# STLINK_V2-1.net
KiCad netlist of a schematic drawn in Altium Designer
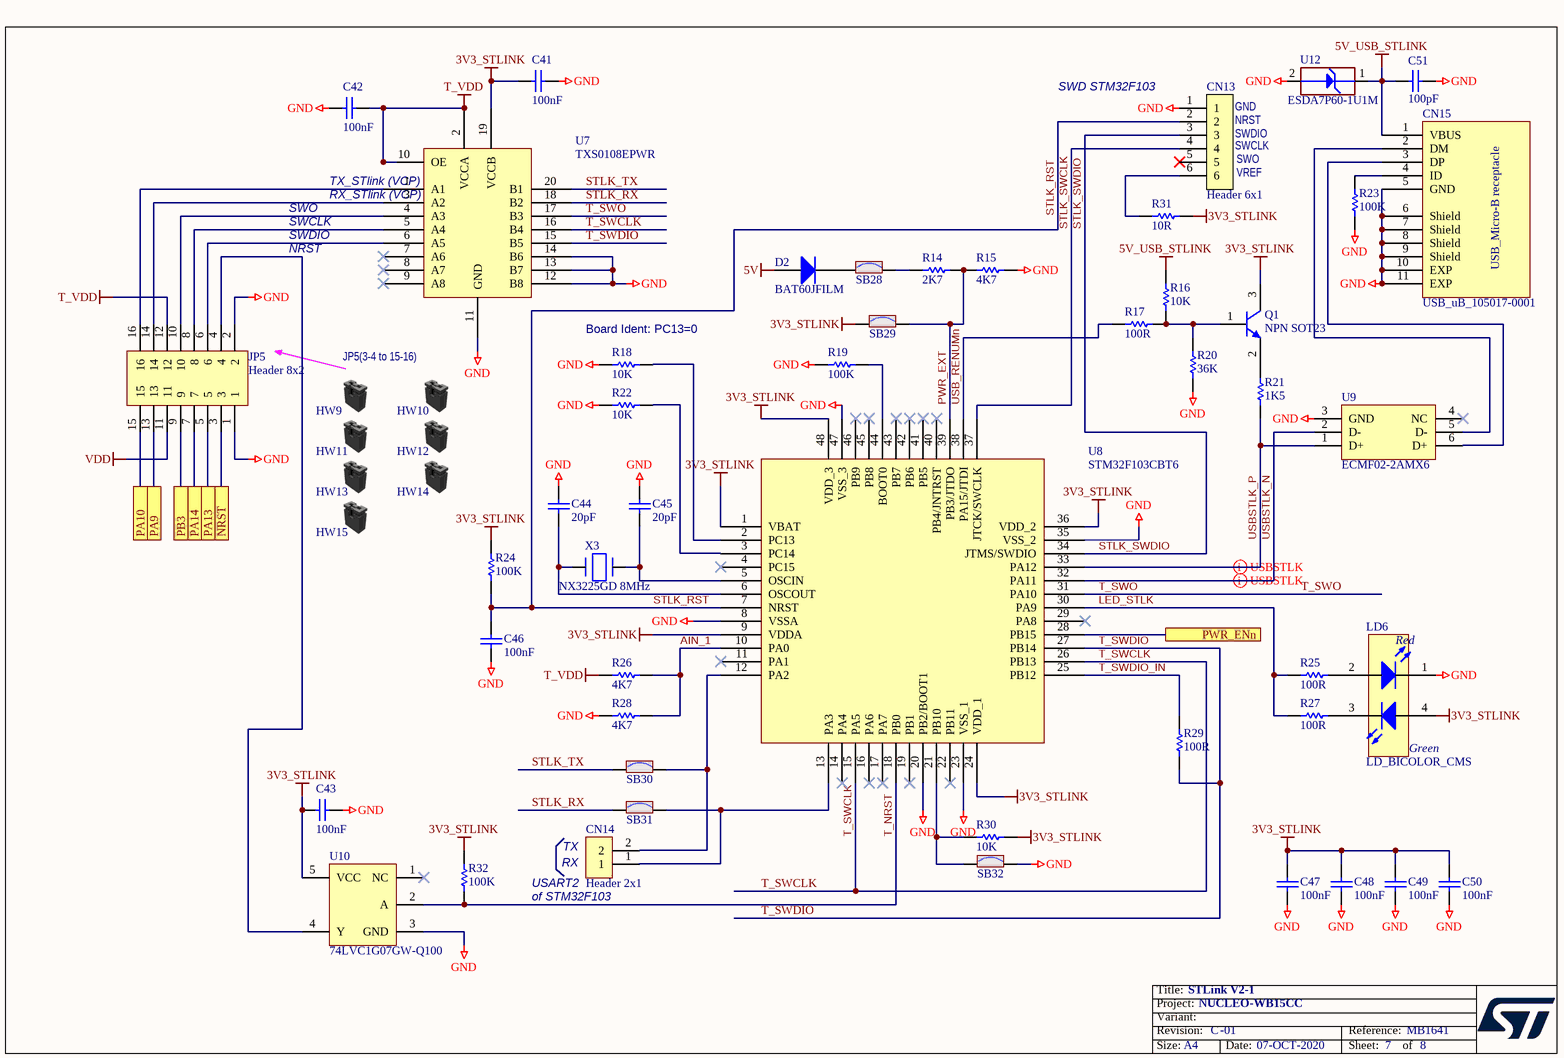
[diagram p0: STLINK_V2-1.SCHDOC]

(export (version "E")
  (design (tool "Eeschema 10.0.6"))
  (components
    (comp (ref "C41")
      (value "100nF")
      (footprint "C0402")
      (description "Capacitor, MLCC, 100nF, 16V, X7R, +/-10%, 0402, T=0.5mm")
      (fields
        (field (name "INTERNAL_PART_NUMBER") "MCD-00006")
        (field (name "MANUFACTURER_PART_NUMBER") "CC0402KRX7R7BB104")
      )
      (libsource (lib "MCD_PARTS_database") (part "Capacitor"))
    )
    (comp (ref "C42")
      (value "100nF")
      (footprint "C0402")
      (description "Capacitor, MLCC, 100nF, 16V, X7R, +/-10%, 0402, T=0.5mm")
      (fields
        (field (name "INTERNAL_PART_NUMBER") "MCD-00006")
        (field (name "MANUFACTURER_PART_NUMBER") "CC0402KRX7R7BB104")
      )
      (libsource (lib "MCD_PARTS_database") (part "Capacitor"))
    )
    (comp (ref "C43")
      (value "100nF")
      (footprint "C0402")
      (description "Capacitor, MLCC, 100nF, 16V, X7R, +/-10%, 0402, T=0.5mm")
      (fields
        (field (name "INTERNAL_PART_NUMBER") "MCD-00006")
        (field (name "MANUFACTURER_PART_NUMBER") "CC0402KRX7R7BB104")
      )
      (libsource (lib "MCD_PARTS_database") (part "Capacitor"))
    )
    (comp (ref "C44")
      (value "20pF")
      (footprint "C0402")
      (description "Capacitor, MLCC, 20pF, 50V, NPO, +/- 5%, 0402, T=0,5mm")
      (fields
        (field (name "INTERNAL_PART_NUMBER") "MCD-00016")
        (field (name "MANUFACTURER_PART_NUMBER") "CC0402JRNPO9BN200")
      )
      (libsource (lib "MCD_PARTS_database") (part "Capacitor"))
    )
    (comp (ref "C45")
      (value "20pF")
      (footprint "C0402")
      (description "Capacitor, MLCC, 20pF, 50V, NPO, +/- 5%, 0402, T=0,5mm")
      (fields
        (field (name "INTERNAL_PART_NUMBER") "MCD-00016")
        (field (name "MANUFACTURER_PART_NUMBER") "CC0402JRNPO9BN200")
      )
      (libsource (lib "MCD_PARTS_database") (part "Capacitor"))
    )
    (comp (ref "C46")
      (value "100nF")
      (footprint "C0402")
      (description "Capacitor, MLCC, 100nF, 16V, X7R, +/-10%, 0402, T=0.5mm")
      (fields
        (field (name "INTERNAL_PART_NUMBER") "MCD-00006")
        (field (name "MANUFACTURER_PART_NUMBER") "CC0402KRX7R7BB104")
      )
      (libsource (lib "MCD_PARTS_database") (part "Capacitor"))
    )
    (comp (ref "C47")
      (value "100nF")
      (footprint "C0402")
      (description "Capacitor, MLCC, 100nF, 16V, X7R, +/-10%, 0402, T=0.5mm")
      (fields
        (field (name "INTERNAL_PART_NUMBER") "MCD-00006")
        (field (name "MANUFACTURER_PART_NUMBER") "CC0402KRX7R7BB104")
      )
      (libsource (lib "MCD_PARTS_database") (part "Capacitor"))
    )
    (comp (ref "C48")
      (value "100nF")
      (footprint "C0402")
      (description "Capacitor, MLCC, 100nF, 16V, X7R, +/-10%, 0402, T=0.5mm")
      (fields
        (field (name "INTERNAL_PART_NUMBER") "MCD-00006")
        (field (name "MANUFACTURER_PART_NUMBER") "CC0402KRX7R7BB104")
      )
      (libsource (lib "MCD_PARTS_database") (part "Capacitor"))
    )
    (comp (ref "C49")
      (value "100nF")
      (footprint "C0402")
      (description "Capacitor, MLCC, 100nF, 16V, X7R, +/-10%, 0402, T=0.5mm")
      (fields
        (field (name "INTERNAL_PART_NUMBER") "MCD-00006")
        (field (name "MANUFACTURER_PART_NUMBER") "CC0402KRX7R7BB104")
      )
      (libsource (lib "MCD_PARTS_database") (part "Capacitor"))
    )
    (comp (ref "C50")
      (value "100nF")
      (footprint "C0402")
      (description "Capacitor, MLCC, 100nF, 16V, X7R, +/-10%, 0402, T=0.5mm")
      (fields
        (field (name "INTERNAL_PART_NUMBER") "MCD-00006")
        (field (name "MANUFACTURER_PART_NUMBER") "CC0402KRX7R7BB104")
      )
      (libsource (lib "MCD_PARTS_database") (part "Capacitor"))
    )
    (comp (ref "C51")
      (value "100pF")
      (footprint "C0402")
      (description "Capacitor,MLCC,100pF,50V,NPO,+/-5%,0402,T=0,5mm")
      (fields
        (field (name "INTERNAL_PART_NUMBER") "MCD-00205")
        (field (name "MANUFACTURER_PART_NUMBER") "CC0402JRNPO9BN101")
      )
      (libsource (lib "MCD_PARTS_database") (part "Capacitor"))
    )
    (comp (ref "CN13")
      (value "Header 6x1")
      (footprint "CON_SAMTEC_TSW-106-07-X-S")
      (description "Header, 6x1, 2,54mm, VR, TH, Height 5.84mm/2.54mm")
      (fields
        (field (name "INTERNAL_PART_NUMBER") "MCD-00212")
        (field (name "MANUFACTURER_PART_NUMBER") "TSW-106-07-G-S")
      )
      (libsource (lib "MCD_PARTS_database") (part "Header 6x1"))
    )
    (comp (ref "CN14")
      (value "Header 2x1")
      (footprint "CON_SAMTEC_TSW-102-07-G-S")
      (description "Header, 2x1, 2,54mm, VR, TH, Height 5.84mm/2.54mm")
      (fields
        (field (name "INTERNAL_PART_NUMBER") "MCD-00032")
        (field (name "MANUFACTURER_PART_NUMBER") "TSW-102-07-G-S")
      )
      (libsource (lib "MCD_PARTS_database") (part "Header 2x1"))
    )
    (comp (ref "CN15")
      (value "USB_uB_105017-0001")
      (footprint "CON_USBMICROB_MOLEX_105017-0001_H2P90")
      (description "USB-MICRO-B, 0.65mm, RA, SMT, Bottom Mount,")
      (fields
        (field (name "INTERNAL_PART_NUMBER") "MCD-00028")
        (field (name "MANUFACTURER_PART_NUMBER") "1050170001")
      )
      (libsource (lib "MCD_PARTS_database") (part "USB_uB_105017.0001"))
    )
    (comp (ref "D2")
      (value "BAT60JFILM")
      (footprint "DIO_SOD323")
      (fields
        (field (name "INTERNAL_PART_NUMBER") "MCD-00034")
        (field (name "MANUFACTURER") "STMICROELECTRONICS")
        (field (name "BMS_PART_NUMBER") "9151097")
      )
      (libsource (lib "MCD_PARTS_database") (part "BAT60JFILM"))
    )
    (comp (ref "HW9")
      (value "Shunt Black 2.54mm")
      (description "SHUNT 2.54mm BLACK")
      (fields
        (field (name "INTERNAL_PART_NUMBER") "MCD-00043")
        (field (name "MANUFACTURER_PART_NUMBER") "SNT-100-BK-G")
      )
      (libsource (lib "MCD_PARTS_database") (part "Shunt Black 2.54mm"))
    )
    (comp (ref "HW10")
      (value "Shunt Black 2.54mm")
      (description "SHUNT 2.54mm BLACK")
      (fields
        (field (name "INTERNAL_PART_NUMBER") "MCD-00043")
        (field (name "MANUFACTURER_PART_NUMBER") "SNT-100-BK-G")
      )
      (libsource (lib "MCD_PARTS_database") (part "Shunt Black 2.54mm"))
    )
    (comp (ref "HW11")
      (value "Shunt Black 2.54mm")
      (description "SHUNT 2.54mm BLACK")
      (fields
        (field (name "INTERNAL_PART_NUMBER") "MCD-00043")
        (field (name "MANUFACTURER_PART_NUMBER") "SNT-100-BK-G")
      )
      (libsource (lib "MCD_PARTS_database") (part "Shunt Black 2.54mm"))
    )
    (comp (ref "HW12")
      (value "Shunt Black 2.54mm")
      (description "SHUNT 2.54mm BLACK")
      (fields
        (field (name "INTERNAL_PART_NUMBER") "MCD-00043")
        (field (name "MANUFACTURER_PART_NUMBER") "SNT-100-BK-G")
      )
      (libsource (lib "MCD_PARTS_database") (part "Shunt Black 2.54mm"))
    )
    (comp (ref "HW13")
      (value "Shunt Black 2.54mm")
      (description "SHUNT 2.54mm BLACK")
      (fields
        (field (name "INTERNAL_PART_NUMBER") "MCD-00043")
        (field (name "MANUFACTURER_PART_NUMBER") "SNT-100-BK-G")
      )
      (libsource (lib "MCD_PARTS_database") (part "Shunt Black 2.54mm"))
    )
    (comp (ref "HW14")
      (value "Shunt Black 2.54mm")
      (description "SHUNT 2.54mm BLACK")
      (fields
        (field (name "INTERNAL_PART_NUMBER") "MCD-00043")
        (field (name "MANUFACTURER_PART_NUMBER") "SNT-100-BK-G")
      )
      (libsource (lib "MCD_PARTS_database") (part "Shunt Black 2.54mm"))
    )
    (comp (ref "HW15")
      (value "Shunt Black 2.54mm")
      (description "SHUNT 2.54mm BLACK")
      (fields
        (field (name "INTERNAL_PART_NUMBER") "MCD-00043")
        (field (name "MANUFACTURER_PART_NUMBER") "SNT-100-BK-G")
      )
      (libsource (lib "MCD_PARTS_database") (part "Shunt Black 2.54mm"))
    )
    (comp (ref "JP5")
      (value "Header 8x2")
      (footprint "CON_SAMTEC_TSW-108-07-X-D")
      (description "Header, 8x2, 2,54mm, VR, TH, Height 5.84mm/2.54mm")
      (fields
        (field (name "INTERNAL_PART_NUMBER") "MCD-02061")
        (field (name "MANUFACTURER_PART_NUMBER") "TSW-108-07-G-D")
      )
      (libsource (lib "MCD_PARTS_database") (part "Header 8x2"))
    )
    (comp (ref "LD6")
      (value "LD_BICOLOR_CMS")
      (footprint "LED_BI-GR_HSMF-A201-A00J1")
      (description "LED Bicolor")
      (fields
        (field (name "INTERNAL_PART_NUMBER") "MCD-00051")
        (field (name "MANUFACTURER_PART_NUMBER") "HSMF-A201-A00J1")
      )
      (libsource (lib "MCD_PARTS_database") (part "LD_BICOLOR_CMS"))
    )
    (comp (ref "Q1")
      (value "NPN SOT23")
      (footprint "NPN_SOT23")
      (description "NPN Bipolar Transistor")
      (fields
        (field (name "INTERNAL_PART_NUMBER") "MCD-00073")
        (field (name "MANUFACTURER_PART_NUMBER") "BSR14")
      )
      (libsource (lib "MCD_PARTS_database") (part "9013-SOT23"))
    )
    (comp (ref "R14")
      (value "2K7")
      (footprint "R0402")
      (description "Resistor,2K7,0402,1%,1/16W")
      (fields
        (field (name "INTERNAL_PART_NUMBER") "MCD-00055")
        (field (name "MANUFACTURER_PART_NUMBER") "RC0402FR-072K7L")
      )
      (libsource (lib "MCD_PARTS_database") (part "Resistor"))
    )
    (comp (ref "R15")
      (value "4K7")
      (footprint "R0402")
      (description "Resistor,4K7,0402,1%,1/16W")
      (fields
        (field (name "INTERNAL_PART_NUMBER") "MCD-00065")
        (field (name "MANUFACTURER_PART_NUMBER") "RC0402FR-074K7L")
      )
      (libsource (lib "MCD_PARTS_database") (part "Resistor"))
    )
    (comp (ref "R16")
      (value "10K")
      (footprint "R0402")
      (description "Resistor,10K,0402,1%,1/16W")
      (fields
        (field (name "INTERNAL_PART_NUMBER") "MCD-00053")
        (field (name "MANUFACTURER_PART_NUMBER") "RC0402FR-0710KL")
      )
      (libsource (lib "MCD_PARTS_database") (part "Resistor"))
    )
    (comp (ref "R17")
      (value "100R")
      (footprint "R0402")
      (description "Resistor,100R,0402,1%,1/16W")
      (fields
        (field (name "INTERNAL_PART_NUMBER") "MCD-00067")
        (field (name "MANUFACTURER_PART_NUMBER") "RC0402FR-07100RL")
      )
      (libsource (lib "MCD_PARTS_database") (part "Resistor"))
    )
    (comp (ref "R18")
      (value "10K")
      (footprint "R0402")
      (description "Resistor,10K,0402,1%,1/16W")
      (fields
        (field (name "INTERNAL_PART_NUMBER") "MCD-00053")
        (field (name "MANUFACTURER_PART_NUMBER") "RC0402FR-0710KL")
      )
      (libsource (lib "MCD_PARTS_database") (part "Resistor"))
    )
    (comp (ref "R19")
      (value "100K")
      (footprint "R0402")
      (description "Resistor,100K,0402,1%,1/16W")
      (fields
        (field (name "INTERNAL_PART_NUMBER") "MCD-00059")
        (field (name "MANUFACTURER_PART_NUMBER") "RC0402FR-07100KL")
      )
      (libsource (lib "MCD_PARTS_database") (part "Resistor"))
    )
    (comp (ref "R20")
      (value "36K")
      (footprint "R0402")
      (description "Resistor,36K,0402,1%,1/16W")
      (fields
        (field (name "INTERNAL_PART_NUMBER") "MCD-00069")
        (field (name "MANUFACTURER_PART_NUMBER") "RC0402FR-0736KL")
      )
      (libsource (lib "MCD_PARTS_database") (part "Resistor"))
    )
    (comp (ref "R21")
      (value "1K5")
      (footprint "R0402")
      (description "Resistor,1K5,0402,1%,1/16W")
      (fields
        (field (name "INTERNAL_PART_NUMBER") "MCD-00068")
        (field (name "MANUFACTURER_PART_NUMBER") "RC0402FR-071K5L")
      )
      (libsource (lib "MCD_PARTS_database") (part "Resistor"))
    )
    (comp (ref "R22")
      (value "10K")
      (footprint "R0402")
      (description "Resistor,10K,0402,1%,1/16W")
      (fields
        (field (name "INTERNAL_PART_NUMBER") "MCD-00053")
        (field (name "MANUFACTURER_PART_NUMBER") "RC0402FR-0710KL")
      )
      (libsource (lib "MCD_PARTS_database") (part "Resistor"))
    )
    (comp (ref "R23")
      (value "100K")
      (footprint "R0402")
      (description "Resistor,100K,0402,1%,1/16W")
      (fields
        (field (name "INTERNAL_PART_NUMBER") "MCD-00059")
        (field (name "MANUFACTURER_PART_NUMBER") "RC0402FR-07100KL")
      )
      (libsource (lib "MCD_PARTS_database") (part "Resistor"))
    )
    (comp (ref "R24")
      (value "100K")
      (footprint "R0402")
      (description "Resistor,100K,0402,1%,1/16W")
      (fields
        (field (name "INTERNAL_PART_NUMBER") "MCD-00059")
        (field (name "MANUFACTURER_PART_NUMBER") "RC0402FR-07100KL")
      )
      (libsource (lib "MCD_PARTS_database") (part "Resistor"))
    )
    (comp (ref "R25")
      (value "100R")
      (footprint "R0402")
      (description "Resistor,100R,0402,1%,1/16W")
      (fields
        (field (name "INTERNAL_PART_NUMBER") "MCD-00067")
        (field (name "MANUFACTURER_PART_NUMBER") "RC0402FR-07100RL")
      )
      (libsource (lib "MCD_PARTS_database") (part "Resistor"))
    )
    (comp (ref "R26")
      (value "4K7")
      (footprint "R0402")
      (description "Resistor,4K7,0402,1%,1/16W")
      (fields
        (field (name "INTERNAL_PART_NUMBER") "MCD-00065")
        (field (name "MANUFACTURER_PART_NUMBER") "RC0402FR-074K7L")
      )
      (libsource (lib "MCD_PARTS_database") (part "Resistor"))
    )
    (comp (ref "R27")
      (value "100R")
      (footprint "R0402")
      (description "Resistor,100R,0402,1%,1/16W")
      (fields
        (field (name "INTERNAL_PART_NUMBER") "MCD-00067")
        (field (name "MANUFACTURER_PART_NUMBER") "RC0402FR-07100RL")
      )
      (libsource (lib "MCD_PARTS_database") (part "Resistor"))
    )
    (comp (ref "R28")
      (value "4K7")
      (footprint "R0402")
      (description "Resistor,4K7,0402,1%,1/16W")
      (fields
        (field (name "INTERNAL_PART_NUMBER") "MCD-00065")
        (field (name "MANUFACTURER_PART_NUMBER") "RC0402FR-074K7L")
      )
      (libsource (lib "MCD_PARTS_database") (part "Resistor"))
    )
    (comp (ref "R29")
      (value "100R")
      (footprint "R0402")
      (description "Resistor,100R,0402,1%,1/16W")
      (fields
        (field (name "INTERNAL_PART_NUMBER") "MCD-00067")
        (field (name "MANUFACTURER_PART_NUMBER") "RC0402FR-07100RL")
      )
      (libsource (lib "MCD_PARTS_database") (part "Resistor"))
    )
    (comp (ref "R30")
      (value "10K")
      (footprint "R0402")
      (description "Resistor,10K,0402,1%,1/16W")
      (fields
        (field (name "INTERNAL_PART_NUMBER") "MCD-00053")
        (field (name "MANUFACTURER_PART_NUMBER") "RC0402FR-0710KL")
      )
      (libsource (lib "MCD_PARTS_database") (part "Resistor"))
    )
    (comp (ref "R31")
      (value "10R")
      (footprint "R0402")
      (description "Resistor,10R,0402,1%,1/16W")
      (fields
        (field (name "INTERNAL_PART_NUMBER") "MCD-00358")
        (field (name "MANUFACTURER_PART_NUMBER") "RC0402FR-0710RL")
      )
      (libsource (lib "MCD_PARTS_database") (part "Resistor"))
    )
    (comp (ref "R32")
      (value "100K")
      (footprint "R0402")
      (description "Resistor,100K,0402,1%,1/16W")
      (fields
        (field (name "INTERNAL_PART_NUMBER") "MCD-00059")
        (field (name "MANUFACTURER_PART_NUMBER") "RC0402FR-07100KL")
      )
      (libsource (lib "MCD_PARTS_database") (part "Resistor"))
    )
    (comp (ref "SB28")
      (value "SB_ON")
      (footprint "SOLDER-BRIDGE_R0402-0R")
      (description "Solder Bridge 0402 ON")
      (fields
        (field (name "INTERNAL_PART_NUMBER") "MCD-01618")
        (field (name "MANUFACTURER_PART_NUMBER") "RC0402JR-070RL")
      )
      (libsource (lib "MCD_PARTS_database") (part "SB_ON"))
    )
    (comp (ref "SB29")
      (value "SB_ON")
      (footprint "SOLDER-BRIDGE_R0402-0R")
      (description "Solder Bridge 0402 ON")
      (fields
        (field (name "INTERNAL_PART_NUMBER") "MCD-01618")
        (field (name "MANUFACTURER_PART_NUMBER") "RC0402JR-070RL")
      )
      (libsource (lib "MCD_PARTS_database") (part "SB_ON"))
    )
    (comp (ref "SB30")
      (value "SB_ON")
      (footprint "SOLDER-BRIDGE_R0402-0R")
      (description "Solder Bridge 0402 ON")
      (fields
        (field (name "INTERNAL_PART_NUMBER") "MCD-01618")
        (field (name "MANUFACTURER_PART_NUMBER") "RC0402JR-070RL")
      )
      (libsource (lib "MCD_PARTS_database") (part "SB_ON"))
    )
    (comp (ref "SB31")
      (value "SB_ON")
      (footprint "SOLDER-BRIDGE_R0402-0R")
      (description "Solder Bridge 0402 ON")
      (fields
        (field (name "INTERNAL_PART_NUMBER") "MCD-01618")
        (field (name "MANUFACTURER_PART_NUMBER") "RC0402JR-070RL")
      )
      (libsource (lib "MCD_PARTS_database") (part "SB_ON"))
    )
    (comp (ref "SB32")
      (value "SB_ON")
      (footprint "SOLDER-BRIDGE_R0402-0R")
      (description "Solder Bridge 0402 ON")
      (fields
        (field (name "INTERNAL_PART_NUMBER") "MCD-01618")
        (field (name "MANUFACTURER_PART_NUMBER") "RC0402JR-070RL")
      )
      (libsource (lib "MCD_PARTS_database") (part "SB_ON"))
    )
    (comp (ref "U7")
      (value "TXS0108EPWR")
      (footprint "ICC_TSSOP20_6P50X4P40_P065")
      (description "8bits_bidirectionnal level shifter, Delay 312ns/1V8")
      (fields
        (field (name "INTERNAL_PART_NUMBER") "MCD-00289")
        (field (name "MANUFACTURER") "TEXAS INSTRUMENTS")
      )
      (libsource (lib "MCD_PARTS_database") (part "TXS0108EPWR"))
    )
    (comp (ref "U8")
      (value "STM32F103CBT6")
      (footprint "ICC_LQFP48_7X7_P050")
      (description "Medium-density performance line ARM-based 32-bit MCU with 128KB Flash")
      (fields
        (field (name "INTERNAL_PART_NUMBER") "MCD-00085")
        (field (name "MANUFACTURER") "STMICROELECTRONICS")
      )
      (libsource (lib "MCD_PARTS_database") (part "STM32F103CBT6"))
    )
    (comp (ref "U9")
      (value "ECMF02-2AMX6")
      (footprint "ESD_QFN-6L_1P7X1P5_P050")
      (description "Common mode filter with ESD protection for USB 2.0 interface")
      (fields
        (field (name "INTERNAL_PART_NUMBER") "MCD-00649")
        (field (name "MANUFACTURER") "STMICROELECTRONICS")
      )
      (libsource (lib "MCD_PARTS_database") (part "ECMF02-2AMX6"))
    )
    (comp (ref "U10")
      (value "74LVC1G07GW-Q100")
      (footprint "ICC_TSSOP5_SOT353-1_2P05X1P25_P065")
      (description "Buffer/Driver 1-CH Non-Inverting Open Drain CMOS Automotive 5-Pin TSSOP T/R")
      (fields (field (name "INTERNAL_PART_NUMBER") "MCD-01960") (field (name "MANUFACTURER") "NEXPERIA"))
      (libsource (lib "MCD_PARTS_database") (part "74LVC1G07GW-Q100"))
    )
    (comp (ref "U12")
      (value "ESDA7P60-1U1M")
      (footprint "ESD_QFN2_1P6X1_P125")
      (description "High power transient voltage suppressor, 7V breakdown")
      (fields
        (field (name "INTERNAL_PART_NUMBER") "MCD-00251")
        (field (name "MANUFACTURER") "STMICROELECTRONICS")
      )
      (libsource (lib "MCD_PARTS_database") (part "ESD-TRANSIL"))
    )
    (comp (ref "X3")
      (value "NX3225GD 8MHz")
      (footprint "CRY_NX3225GD_2P")
      (description "Crystal 8MHz, 8pF, +-20ppm, 500ohms max,  SMD")
      (fields
        (field (name "INTERNAL_PART_NUMBER") "MCD-00092")
        (field (name "MANUFACTURER_PART_NUMBER") "NX3225GD 8MHz EXS00A-CG04874")
      )
      (libsource (lib "MCD_PARTS_database") (part "XTAL_2_PINS"))
    )
  )
  (nets
    (net (code "1") (name "/AIN_1") (class "Default")
      (node (ref "R26") (pin "2") (pinfunction "2_2") (pintype "passive"))
      (node (ref "R28") (pin "2") (pinfunction "2_2") (pintype "passive"))
      (node (ref "U8") (pin "10") (pinfunction "PA0_10") (pintype "passive"))
    )
    (net (code "2") (name "/LED_STLK") (class "Default")
      (node (ref "R25") (pin "1") (pinfunction "1_1") (pintype "passive"))
      (node (ref "R27") (pin "1") (pinfunction "1_1") (pintype "passive"))
      (node (ref "U8") (pin "30") (pinfunction "PA9_30") (pintype "passive"))
    )
    (net (code "3") (name "/NRST") (class "Default")
      (node (ref "JP5") (pin "3") (pinfunction "3_3") (pintype "passive"))
    )
    (net (code "4") (name "/PA9") (class "Default")
      (node (ref "JP5") (pin "13") (pinfunction "13_13") (pintype "passive"))
    )
    (net (code "5") (name "/PA10") (class "Default")
      (node (ref "JP5") (pin "15") (pinfunction "15_15") (pintype "passive"))
    )
    (net (code "6") (name "/PA13") (class "Default")
      (node (ref "JP5") (pin "5") (pinfunction "5_5") (pintype "passive"))
    )
    (net (code "7") (name "/PA14") (class "Default")
      (node (ref "JP5") (pin "7") (pinfunction "7_7") (pintype "passive"))
    )
    (net (code "8") (name "/PB3") (class "Default")
      (node (ref "JP5") (pin "9") (pinfunction "9_9") (pintype "passive"))
    )
    (net (code "9") (name "/PWR_ENn") (class "Default")
      (node (ref "U8") (pin "28") (pinfunction "PB15_28") (pintype "passive"))
    )
    (net (code "10") (name "/PWR_EXT") (class "Default")
      (node (ref "R14") (pin "2") (pinfunction "2_2") (pintype "passive"))
      (node (ref "R15") (pin "1") (pinfunction "1_1") (pintype "passive"))
      (node (ref "SB29") (pin "2") (pinfunction "2_2") (pintype "passive"))
      (node (ref "U8") (pin "39") (pinfunction "PB3/JTDO_39") (pintype "passive"))
    )
    (net (code "11") (name "/STLK_RST") (class "Default")
      (node (ref "C46") (pin "2") (pinfunction "2_2") (pintype "passive"))
      (node (ref "CN13") (pin "2") (pinfunction "2_2") (pintype "passive"))
      (node (ref "R24") (pin "1") (pinfunction "1_1") (pintype "passive"))
      (node (ref "U8") (pin "7") (pinfunction "NRST_7") (pintype "passive"))
    )
    (net (code "12") (name "/STLK_RX") (class "Default")
      (node (ref "SB31") (pin "1") (pinfunction "1_1") (pintype "passive"))
      (node (ref "U7") (pin "18") (pinfunction "B2_18") (pintype "passive"))
    )
    (net (code "13") (name "/STLK_SWCLK") (class "Default")
      (node (ref "CN13") (pin "4") (pinfunction "4_4") (pintype "passive"))
      (node (ref "U8") (pin "37") (pinfunction "JTCK/SWCLK_37") (pintype "passive"))
    )
    (net (code "14") (name "/STLK_SWDIO") (class "Default")
      (node (ref "CN13") (pin "3") (pinfunction "3_3") (pintype "passive"))
      (node (ref "U8") (pin "34") (pinfunction "JTMS/SWDIO_34") (pintype "passive"))
    )
    (net (code "15") (name "/STLK_TX") (class "Default")
      (node (ref "SB30") (pin "1") (pinfunction "1_1") (pintype "passive"))
      (node (ref "U7") (pin "20") (pinfunction "B1_20") (pintype "passive"))
    )
    (net (code "16") (name "/T_NRST") (class "Default")
      (node (ref "R32") (pin "1") (pinfunction "1_1") (pintype "passive"))
      (node (ref "U10") (pin "2") (pinfunction "A_2") (pintype "passive"))
      (node (ref "U8") (pin "18") (pinfunction "PB0_18") (pintype "passive"))
    )
    (net (code "17") (name "/T_SWCLK") (class "Default")
      (node (ref "U7") (pin "16") (pinfunction "B4_16") (pintype "passive"))
      (node (ref "U8") (pin "15") (pinfunction "PA5_15") (pintype "passive"))
      (node (ref "U8") (pin "26") (pinfunction "PB13_26") (pintype "passive"))
    )
    (net (code "18") (name "/T_SWDIO") (class "Default")
      (node (ref "R29") (pin "1") (pinfunction "1_1") (pintype "passive"))
      (node (ref "U7") (pin "15") (pinfunction "B5_15") (pintype "passive"))
      (node (ref "U8") (pin "27") (pinfunction "PB14_27") (pintype "passive"))
    )
    (net (code "19") (name "/T_SWDIO_IN") (class "Default")
      (node (ref "R29") (pin "2") (pinfunction "2_2") (pintype "passive"))
      (node (ref "U8") (pin "25") (pinfunction "PB12_25") (pintype "passive"))
    )
    (net (code "20") (name "/T_SWO") (class "Default")
      (node (ref "U7") (pin "17") (pinfunction "B3_17") (pintype "passive"))
      (node (ref "U8") (pin "31") (pinfunction "PA10_31") (pintype "passive"))
    )
    (net (code "21") (name "/USBSTLK_N") (class "Default")
      (node (ref "U8") (pin "32") (pinfunction "PA11_32") (pintype "passive"))
      (node (ref "U9") (pin "2") (pinfunction "D-_2") (pintype "passive"))
    )
    (net (code "22") (name "/USBSTLK_P") (class "Default")
      (node (ref "R21") (pin "1") (pinfunction "1_1") (pintype "passive"))
      (node (ref "U8") (pin "33") (pinfunction "PA12_33") (pintype "passive"))
      (node (ref "U9") (pin "1") (pinfunction "D+_1") (pintype "passive"))
    )
    (net (code "23") (name "/USB_RENUMn") (class "Default")
      (node (ref "R17") (pin "1") (pinfunction "1_1") (pintype "passive"))
      (node (ref "U8") (pin "38") (pinfunction "PA15/JTDI_38") (pintype "passive"))
    )
    (net (code "24") (name "3V3_STLINK") (class "Default")
      (node (ref "C41") (pin "1") (pinfunction "1_1") (pintype "passive"))
      (node (ref "C43") (pin "1") (pinfunction "1_1") (pintype "passive"))
      (node (ref "C47") (pin "2") (pinfunction "2_2") (pintype "passive"))
      (node (ref "C48") (pin "2") (pinfunction "2_2") (pintype "passive"))
      (node (ref "C49") (pin "2") (pinfunction "2_2") (pintype "passive"))
      (node (ref "C50") (pin "2") (pinfunction "2_2") (pintype "passive"))
      (node (ref "LD6") (pin "4") (pinfunction "YellowGreen_anode_4") (pintype "passive"))
      (node (ref "Q1") (pin "3") (pinfunction "C_3") (pintype "passive"))
      (node (ref "R24") (pin "2") (pinfunction "2_2") (pintype "passive"))
      (node (ref "R30") (pin "1") (pinfunction "1_1") (pintype "passive"))
      (node (ref "R31") (pin "2") (pinfunction "2_2") (pintype "passive"))
      (node (ref "R32") (pin "2") (pinfunction "2_2") (pintype "passive"))
      (node (ref "SB29") (pin "1") (pinfunction "1_1") (pintype "passive"))
      (node (ref "U10") (pin "5") (pinfunction "VCC_5") (pintype "passive"))
      (node (ref "U7") (pin "19") (pinfunction "VCCB_19") (pintype "passive"))
      (node (ref "U8") (pin "1") (pinfunction "VBAT_1") (pintype "passive"))
      (node (ref "U8") (pin "24") (pinfunction "VDD_1_24") (pintype "passive"))
      (node (ref "U8") (pin "36") (pinfunction "VDD_2_36") (pintype "passive"))
      (node (ref "U8") (pin "48") (pinfunction "VDD_3_48") (pintype "passive"))
      (node (ref "U8") (pin "9") (pinfunction "VDDA_9") (pintype "passive"))
    )
    (net (code "25") (name "5V") (class "Default")
      (node (ref "D2") (pin "1") (pinfunction "A_1") (pintype "passive"))
    )
    (net (code "26") (name "5V_USB_STLINK") (class "Default")
      (node (ref "C51") (pin "1") (pinfunction "1_1") (pintype "passive"))
      (node (ref "CN15") (pin "1") (pinfunction "VBUS_1") (pintype "passive"))
      (node (ref "R16") (pin "2") (pinfunction "2_2") (pintype "passive"))
      (node (ref "U12") (pin "1") (pinfunction "IO1_1") (pintype "passive"))
    )
    (net (code "27") (name "GND") (class "Default")
      (node (ref "C41") (pin "2") (pinfunction "2_2") (pintype "passive"))
      (node (ref "C42") (pin "1") (pinfunction "1_1") (pintype "passive"))
      (node (ref "C43") (pin "2") (pinfunction "2_2") (pintype "passive"))
      (node (ref "C44") (pin "2") (pinfunction "2_2") (pintype "passive"))
      (node (ref "C45") (pin "2") (pinfunction "2_2") (pintype "passive"))
      (node (ref "C46") (pin "1") (pinfunction "1_1") (pintype "passive"))
      (node (ref "C47") (pin "1") (pinfunction "1_1") (pintype "passive"))
      (node (ref "C48") (pin "1") (pinfunction "1_1") (pintype "passive"))
      (node (ref "C49") (pin "1") (pinfunction "1_1") (pintype "passive"))
      (node (ref "C50") (pin "1") (pinfunction "1_1") (pintype "passive"))
      (node (ref "C51") (pin "2") (pinfunction "2_2") (pintype "passive"))
      (node (ref "CN13") (pin "1") (pinfunction "1_1") (pintype "passive"))
      (node (ref "CN15") (pin "10") (pinfunction "EXP_10") (pintype "passive"))
      (node (ref "CN15") (pin "11") (pinfunction "EXP_11") (pintype "passive"))
      (node (ref "CN15") (pin "5") (pinfunction "GND_5") (pintype "passive"))
      (node (ref "CN15") (pin "6") (pinfunction "Shield_6") (pintype "passive"))
      (node (ref "CN15") (pin "7") (pinfunction "Shield_7") (pintype "passive"))
      (node (ref "CN15") (pin "8") (pinfunction "Shield_8") (pintype "passive"))
      (node (ref "CN15") (pin "9") (pinfunction "Shield_9") (pintype "passive"))
      (node (ref "JP5") (pin "1") (pinfunction "1_1") (pintype "passive"))
      (node (ref "JP5") (pin "2") (pinfunction "2_2") (pintype "passive"))
      (node (ref "LD6") (pin "1") (pinfunction "RED_cathode_1") (pintype "passive"))
      (node (ref "R15") (pin "2") (pinfunction "2_2") (pintype "passive"))
      (node (ref "R18") (pin "2") (pinfunction "2_2") (pintype "passive"))
      (node (ref "R19") (pin "2") (pinfunction "2_2") (pintype "passive"))
      (node (ref "R20") (pin "1") (pinfunction "1_1") (pintype "passive"))
      (node (ref "R22") (pin "2") (pinfunction "2_2") (pintype "passive"))
      (node (ref "R23") (pin "1") (pinfunction "1_1") (pintype "passive"))
      (node (ref "R28") (pin "1") (pinfunction "1_1") (pintype "passive"))
      (node (ref "SB32") (pin "2") (pinfunction "2_2") (pintype "passive"))
      (node (ref "U10") (pin "3") (pinfunction "GND_3") (pintype "passive"))
      (node (ref "U12") (pin "2") (pinfunction "GND_2") (pintype "passive"))
      (node (ref "U7") (pin "11") (pinfunction "GND_11") (pintype "passive"))
      (node (ref "U7") (pin "12") (pinfunction "B8_12") (pintype "passive"))
      (node (ref "U7") (pin "13") (pinfunction "B7_13") (pintype "passive"))
      (node (ref "U7") (pin "14") (pinfunction "B6_14") (pintype "passive"))
      (node (ref "U8") (pin "20") (pinfunction "PB2/BOOT1_20") (pintype "passive"))
      (node (ref "U8") (pin "23") (pinfunction "VSS_1_23") (pintype "passive"))
      (node (ref "U8") (pin "35") (pinfunction "VSS_2_35") (pintype "passive"))
      (node (ref "U8") (pin "47") (pinfunction "VSS_3_47") (pintype "passive"))
      (node (ref "U8") (pin "8") (pinfunction "VSSA_8") (pintype "passive"))
      (node (ref "U9") (pin "3") (pinfunction "GND_3") (pintype "passive"))
    )
    (net (code "28") (name "Net-(CN13-Pad6)") (class "Default")
      (node (ref "CN13") (pin "6") (pinfunction "6_6") (pintype "passive"))
      (node (ref "R31") (pin "1") (pinfunction "1_1") (pintype "passive"))
    )
    (net (code "29") (name "Net-(CN15-DM)") (class "Default")
      (node (ref "CN15") (pin "2") (pinfunction "DM_2") (pintype "passive"))
      (node (ref "U9") (pin "5") (pinfunction "D-_5") (pintype "passive"))
    )
    (net (code "30") (name "Net-(CN15-DP)") (class "Default")
      (node (ref "CN15") (pin "3") (pinfunction "DP_3") (pintype "passive"))
      (node (ref "U9") (pin "6") (pinfunction "D+_6") (pintype "passive"))
    )
    (net (code "31") (name "Net-(CN15-ID)") (class "Default")
      (node (ref "CN15") (pin "4") (pinfunction "ID_4") (pintype "passive"))
      (node (ref "R23") (pin "2") (pinfunction "2_2") (pintype "passive"))
    )
    (net (code "32") (name "Net-(D2-K)") (class "Default")
      (node (ref "D2") (pin "2") (pinfunction "K_2") (pintype "passive"))
      (node (ref "SB28") (pin "1") (pinfunction "1_1") (pintype "passive"))
    )
    (net (code "33") (name "Net-(LD6-Red_anode)") (class "Default")
      (node (ref "LD6") (pin "2") (pinfunction "Red_anode_2") (pintype "passive"))
      (node (ref "R25") (pin "2") (pinfunction "2_2") (pintype "passive"))
    )
    (net (code "34") (name "Net-(LD6-YellowGreen_cathode)") (class "Default")
      (node (ref "LD6") (pin "3") (pinfunction "YellowGreen_cathode_3") (pintype "passive"))
      (node (ref "R27") (pin "2") (pinfunction "2_2") (pintype "passive"))
    )
    (net (code "35") (name "Net-(Q1-B)") (class "Default")
      (node (ref "Q1") (pin "1") (pinfunction "B_1") (pintype "passive"))
      (node (ref "R16") (pin "1") (pinfunction "1_1") (pintype "passive"))
      (node (ref "R17") (pin "2") (pinfunction "2_2") (pintype "passive"))
      (node (ref "R20") (pin "2") (pinfunction "2_2") (pintype "passive"))
    )
    (net (code "36") (name "Net-(Q1-E)") (class "Default")
      (node (ref "Q1") (pin "2") (pinfunction "E_2") (pintype "passive"))
      (node (ref "R21") (pin "2") (pinfunction "2_2") (pintype "passive"))
    )
    (net (code "37") (name "Net-(R14-Pad1)") (class "Default")
      (node (ref "R14") (pin "1") (pinfunction "1_1") (pintype "passive"))
      (node (ref "SB28") (pin "2") (pinfunction "2_2") (pintype "passive"))
    )
    (net (code "38") (name "Net-(U7-A1)") (class "Default")
      (node (ref "JP5") (pin "16") (pinfunction "16_16") (pintype "passive"))
      (node (ref "U7") (pin "1") (pinfunction "A1_1") (pintype "passive"))
    )
    (net (code "39") (name "Net-(U7-A2)") (class "Default")
      (node (ref "JP5") (pin "14") (pinfunction "14_14") (pintype "passive"))
      (node (ref "U7") (pin "3") (pinfunction "A2_3") (pintype "passive"))
    )
    (net (code "40") (name "Net-(U7-A3)") (class "Default")
      (node (ref "JP5") (pin "10") (pinfunction "10_10") (pintype "passive"))
      (node (ref "U7") (pin "4") (pinfunction "A3_4") (pintype "passive"))
    )
    (net (code "41") (name "Net-(U7-A4)") (class "Default")
      (node (ref "JP5") (pin "8") (pinfunction "8_8") (pintype "passive"))
      (node (ref "U7") (pin "5") (pinfunction "A4_5") (pintype "passive"))
    )
    (net (code "42") (name "Net-(U7-A5)") (class "Default")
      (node (ref "JP5") (pin "6") (pinfunction "6_6") (pintype "passive"))
      (node (ref "U7") (pin "6") (pinfunction "A5_6") (pintype "passive"))
    )
    (net (code "43") (name "Net-(U8-BOOT0)") (class "Default")
      (node (ref "R19") (pin "1") (pinfunction "1_1") (pintype "passive"))
      (node (ref "U8") (pin "44") (pinfunction "BOOT0_44") (pintype "passive"))
    )
    (net (code "44") (name "Net-(U8-OSCIN)") (class "Default")
      (node (ref "C45") (pin "1") (pinfunction "1_1") (pintype "passive"))
      (node (ref "U8") (pin "5") (pinfunction "OSCIN_5") (pintype "passive"))
      (node (ref "X3") (pin "2") (pinfunction "X2_2") (pintype "passive"))
    )
    (net (code "45") (name "Net-(U8-OSCOUT)") (class "Default")
      (node (ref "C44") (pin "1") (pinfunction "1_1") (pintype "passive"))
      (node (ref "U8") (pin "6") (pinfunction "OSCOUT_6") (pintype "passive"))
      (node (ref "X3") (pin "1") (pinfunction "X1_1") (pintype "passive"))
    )
    (net (code "46") (name "Net-(U8-PA2)") (class "Default")
      (node (ref "CN14") (pin "2") (pinfunction "2_2") (pintype "passive"))
      (node (ref "SB30") (pin "2") (pinfunction "2_2") (pintype "passive"))
      (node (ref "U8") (pin "12") (pinfunction "PA2_12") (pintype "passive"))
    )
    (net (code "47") (name "Net-(U8-PA3)") (class "Default")
      (node (ref "CN14") (pin "1") (pinfunction "1_1") (pintype "passive"))
      (node (ref "SB31") (pin "2") (pinfunction "2_2") (pintype "passive"))
      (node (ref "U8") (pin "13") (pinfunction "PA3_13") (pintype "passive"))
    )
    (net (code "48") (name "Net-(U8-PB10)") (class "Default")
      (node (ref "R30") (pin "2") (pinfunction "2_2") (pintype "passive"))
      (node (ref "SB32") (pin "1") (pinfunction "1_1") (pintype "passive"))
      (node (ref "U8") (pin "21") (pinfunction "PB10_21") (pintype "passive"))
    )
    (net (code "49") (name "Net-(U8-PC13)") (class "Default")
      (node (ref "R18") (pin "1") (pinfunction "1_1") (pintype "passive"))
      (node (ref "U8") (pin "2") (pinfunction "PC13_2") (pintype "passive"))
    )
    (net (code "50") (name "Net-(U8-PC14)") (class "Default")
      (node (ref "R22") (pin "1") (pinfunction "1_1") (pintype "passive"))
      (node (ref "U8") (pin "3") (pinfunction "PC14_3") (pintype "passive"))
    )
    (net (code "51") (name "Net-(U10-Y)") (class "Default")
      (node (ref "JP5") (pin "4") (pinfunction "4_4") (pintype "passive"))
      (node (ref "U10") (pin "4") (pinfunction "Y_4") (pintype "passive"))
    )
    (net (code "52") (name "T_VDD") (class "Default")
      (node (ref "C42") (pin "2") (pinfunction "2_2") (pintype "passive"))
      (node (ref "JP5") (pin "12") (pinfunction "12_12") (pintype "passive"))
      (node (ref "R26") (pin "1") (pinfunction "1_1") (pintype "passive"))
      (node (ref "U7") (pin "10") (pinfunction "OE_10") (pintype "passive"))
      (node (ref "U7") (pin "2") (pinfunction "VCCA_2") (pintype "passive"))
    )
    (net (code "53") (name "VDD") (class "Default")
      (node (ref "JP5") (pin "11") (pinfunction "11_11") (pintype "passive"))
    )
    (net (code "54") (name "unconnected-(CN13-Pad5)") (class "Default")
      (node (ref "CN13") (pin "5") (pinfunction "5_5") (pintype "passive+no_connect"))
    )
    (net (code "55") (name "unconnected-(U7-A6-Pad7)") (class "Default")
      (node (ref "U7") (pin "7") (pinfunction "A6_7") (pintype "passive+no_connect"))
    )
    (net (code "56") (name "unconnected-(U7-A7-Pad8)") (class "Default")
      (node (ref "U7") (pin "8") (pinfunction "A7_8") (pintype "passive+no_connect"))
    )
    (net (code "57") (name "unconnected-(U7-A8-Pad9)") (class "Default")
      (node (ref "U7") (pin "9") (pinfunction "A8_9") (pintype "passive+no_connect"))
    )
    (net (code "58") (name "unconnected-(U8-PA1-Pad11)") (class "Default")
      (node (ref "U8") (pin "11") (pinfunction "PA1_11") (pintype "passive+no_connect"))
    )
    (net (code "59") (name "unconnected-(U8-PA4-Pad14)") (class "Default")
      (node (ref "U8") (pin "14") (pinfunction "PA4_14") (pintype "passive+no_connect"))
    )
    (net (code "60") (name "unconnected-(U8-PA6-Pad16)") (class "Default")
      (node (ref "U8") (pin "16") (pinfunction "PA6_16") (pintype "passive+no_connect"))
    )
    (net (code "61") (name "unconnected-(U8-PA7-Pad17)") (class "Default")
      (node (ref "U8") (pin "17") (pinfunction "PA7_17") (pintype "passive+no_connect"))
    )
    (net (code "62") (name "unconnected-(U8-PA8-Pad29)") (class "Default")
      (node (ref "U8") (pin "29") (pinfunction "PA8_29") (pintype "passive+no_connect"))
    )
    (net (code "63") (name "unconnected-(U8-PB1-Pad19)") (class "Default")
      (node (ref "U8") (pin "19") (pinfunction "PB1_19") (pintype "passive+no_connect"))
    )
    (net (code "64") (name "unconnected-(U8-PB4{slash}JNTRST-Pad40)") (class "Default")
      (node (ref "U8") (pin "40") (pinfunction "PB4/JNTRST_40") (pintype "passive+no_connect"))
    )
    (net (code "65") (name "unconnected-(U8-PB5-Pad41)") (class "Default")
      (node (ref "U8") (pin "41") (pinfunction "PB5_41") (pintype "passive+no_connect"))
    )
    (net (code "66") (name "unconnected-(U8-PB6-Pad42)") (class "Default")
      (node (ref "U8") (pin "42") (pinfunction "PB6_42") (pintype "passive+no_connect"))
    )
    (net (code "67") (name "unconnected-(U8-PB7-Pad43)") (class "Default")
      (node (ref "U8") (pin "43") (pinfunction "PB7_43") (pintype "passive+no_connect"))
    )
    (net (code "68") (name "unconnected-(U8-PB8-Pad45)") (class "Default")
      (node (ref "U8") (pin "45") (pinfunction "PB8_45") (pintype "passive+no_connect"))
    )
    (net (code "69") (name "unconnected-(U8-PB9-Pad46)") (class "Default")
      (node (ref "U8") (pin "46") (pinfunction "PB9_46") (pintype "passive+no_connect"))
    )
    (net (code "70") (name "unconnected-(U8-PB11-Pad22)") (class "Default")
      (node (ref "U8") (pin "22") (pinfunction "PB11_22") (pintype "passive+no_connect"))
    )
    (net (code "71") (name "unconnected-(U8-PC15-Pad4)") (class "Default")
      (node (ref "U8") (pin "4") (pinfunction "PC15_4") (pintype "passive+no_connect"))
    )
    (net (code "72") (name "unconnected-(U9-NC-Pad4)") (class "Default")
      (node (ref "U9") (pin "4") (pinfunction "NC_4") (pintype "passive+no_connect"))
    )
    (net (code "73") (name "unconnected-(U10-NC-Pad1)") (class "Default")
      (node (ref "U10") (pin "1") (pinfunction "NC_1") (pintype "passive+no_connect"))
    )
  )
)
